# RELAY.net
KiCad netlist of a schematic drawn in Altium Designer
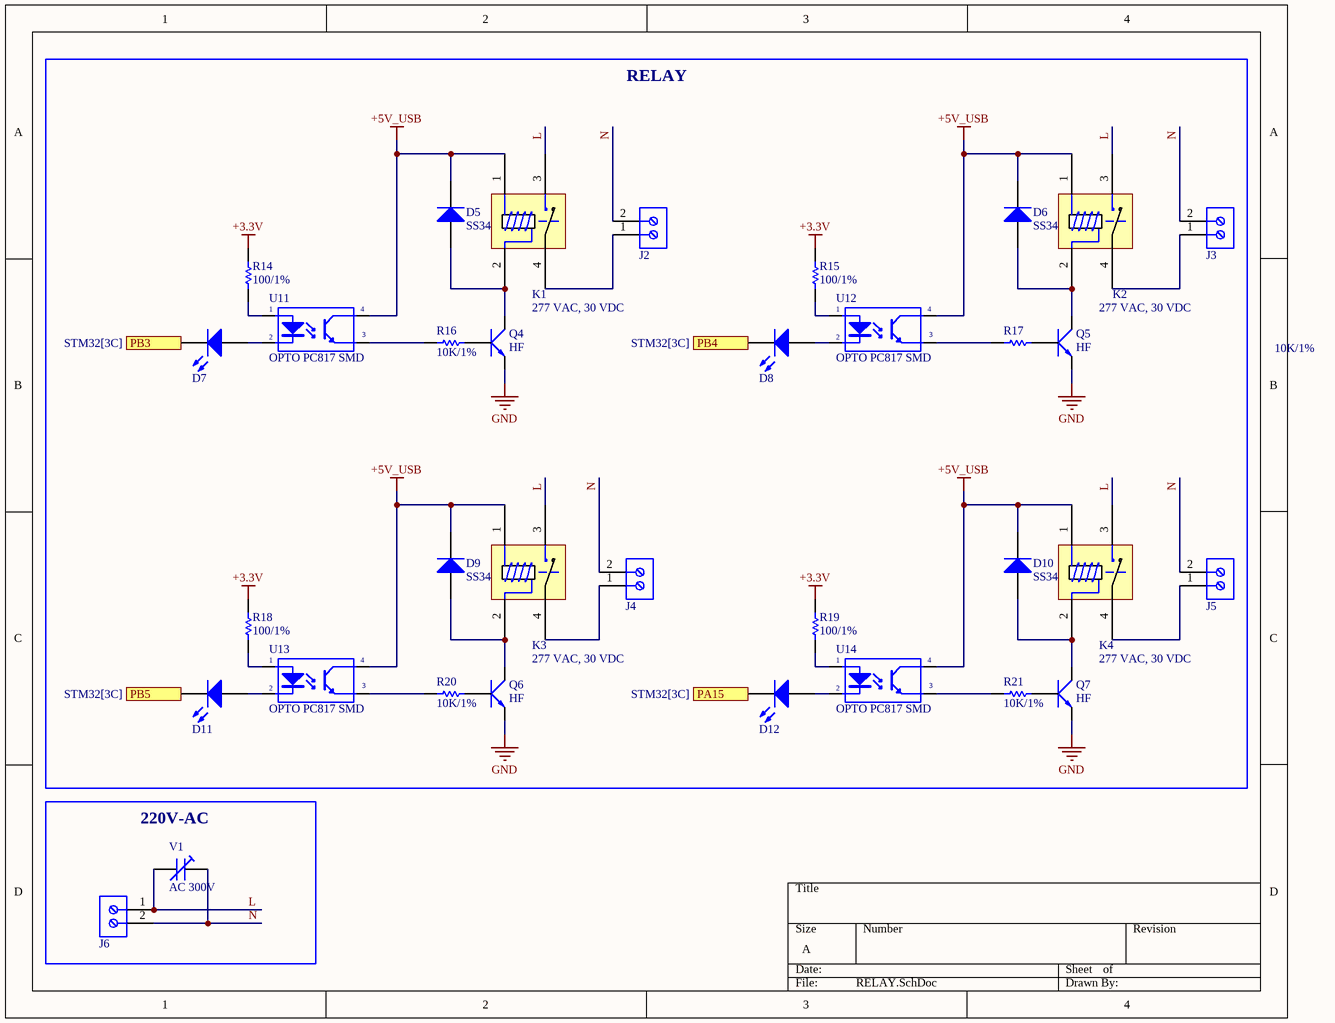
[diagram p0: RELAY.SchDoc]

(export (version "E")
  (design (tool "Eeschema 10.0.6"))
  (components
    (comp (ref "D5")
      (value "SS34")
      (footprint "DIODE SMA")
      (description "Dán")
      (libsource (lib "Altium_Lib_by_KhueNguyenCreator") (part "Diode SS34 ( 1N5822 )"))
    )
    (comp (ref "D6")
      (value "SS34")
      (footprint "DIODE SMA")
      (description "Dán")
      (libsource (lib "Altium_Lib_by_KhueNguyenCreator") (part "Diode SS34 ( 1N5822 )"))
    )
    (comp (ref "D7")
      (value "LED SMD")
      (footprint "LED_0805_Blue")
      (description "LED")
      (libsource (lib "PIF_Library") (part "LED SMD"))
    )
    (comp (ref "D8")
      (value "LED SMD")
      (footprint "LED_0805_Blue")
      (description "LED")
      (libsource (lib "PIF_Library") (part "LED SMD"))
    )
    (comp (ref "D9")
      (value "SS34")
      (footprint "DIODE SMA")
      (description "Dán")
      (libsource (lib "Altium_Lib_by_KhueNguyenCreator") (part "Diode SS34 ( 1N5822 )"))
    )
    (comp (ref "D10")
      (value "SS34")
      (footprint "DIODE SMA")
      (description "Dán")
      (libsource (lib "Altium_Lib_by_KhueNguyenCreator") (part "Diode SS34 ( 1N5822 )"))
    )
    (comp (ref "D11")
      (value "LED SMD")
      (footprint "LED_0805_Blue")
      (description "LED")
      (libsource (lib "PIF_Library") (part "LED SMD"))
    )
    (comp (ref "D12")
      (value "LED SMD")
      (footprint "LED_0805_Blue")
      (description "LED")
      (libsource (lib "PIF_Library") (part "LED SMD"))
    )
    (comp (ref "J2")
      (value "10A, 300V")
      (footprint "691214110002")
      (description "WR-TBL Series 2141 Horizontal Entry Modular, THT, pitch 3.5mm, 2p")
      (fields
        (field (name "MANUFACTURER PART NUMBER") "691214110002")
        (field (name "MANUFACTURER") "Wurth Elektronik")
      )
      (libsource (lib "Altium_Terminal_Block") (part "691214110002"))
    )
    (comp (ref "J3")
      (value "10A, 300V")
      (footprint "691214110002")
      (description "WR-TBL Series 2141 Horizontal Entry Modular, THT, pitch 3.5mm, 2p")
      (fields
        (field (name "MANUFACTURER PART NUMBER") "691214110002")
        (field (name "MANUFACTURER") "Wurth Elektronik")
      )
      (libsource (lib "Altium_Terminal_Block") (part "691214110002"))
    )
    (comp (ref "J4")
      (value "10A, 300V")
      (footprint "691214110002")
      (description "WR-TBL Series 2141 Horizontal Entry Modular, THT, pitch 3.5mm, 2p")
      (fields
        (field (name "MANUFACTURER PART NUMBER") "691214110002")
        (field (name "MANUFACTURER") "Wurth Elektronik")
      )
      (libsource (lib "Altium_Terminal_Block") (part "691214110002"))
    )
    (comp (ref "J5")
      (value "10A, 300V")
      (footprint "691214110002")
      (description "WR-TBL Series 2141 Horizontal Entry Modular, THT, pitch 3.5mm, 2p")
      (fields
        (field (name "MANUFACTURER PART NUMBER") "691214110002")
        (field (name "MANUFACTURER") "Wurth Elektronik")
      )
      (libsource (lib "Altium_Terminal_Block") (part "691214110002"))
    )
    (comp (ref "J6")
      (value "10A, 300V")
      (footprint "691214110002")
      (description "WR-TBL Series 2141 Horizontal Entry Modular, THT, pitch 3.5mm, 2p")
      (fields
        (field (name "MANUFACTURER PART NUMBER") "691214110002")
        (field (name "MANUFACTURER") "Wurth Elektronik")
      )
      (libsource (lib "Altium_Terminal_Block") (part "691214110002"))
    )
    (comp (ref "K1")
      (value "277 VAC, 30 VDC")
      (footprint "HF46F")
      (description "Coil Voltage: 12 VDC; Contact Current Rating: 7A; Switching Voltage Max: 277 VAC, 30 VDC")
      (libsource (lib "Altium_Relay") (part "HF46F-G 12-HS1"))
    )
    (comp (ref "K2")
      (value "277 VAC, 30 VDC")
      (footprint "HF46F")
      (description "Coil Voltage: 12 VDC; Contact Current Rating: 7A; Switching Voltage Max: 277 VAC, 30 VDC")
      (libsource (lib "Altium_Relay") (part "HF46F-G 12-HS1"))
    )
    (comp (ref "K3")
      (value "277 VAC, 30 VDC")
      (footprint "HF46F")
      (description "Coil Voltage: 12 VDC; Contact Current Rating: 7A; Switching Voltage Max: 277 VAC, 30 VDC")
      (libsource (lib "Altium_Relay") (part "HF46F-G 12-HS1"))
    )
    (comp (ref "K4")
      (value "277 VAC, 30 VDC")
      (footprint "HF46F")
      (description "Coil Voltage: 12 VDC; Contact Current Rating: 7A; Switching Voltage Max: 277 VAC, 30 VDC")
      (libsource (lib "Altium_Relay") (part "HF46F-G 12-HS1"))
    )
    (comp (ref "Q4")
      (value "HF")
      (footprint "SOT-23")
      (description "SOT-23")
      (libsource (lib "Altium_Lib_by_KhueNguyenCreator") (part "Trans C1815 HF SMD"))
    )
    (comp (ref "Q5")
      (value "HF")
      (footprint "SOT-23")
      (description "SOT-23")
      (libsource (lib "Altium_Lib_by_KhueNguyenCreator") (part "Trans C1815 HF SMD"))
    )
    (comp (ref "Q6")
      (value "HF")
      (footprint "SOT-23")
      (description "SOT-23")
      (libsource (lib "Altium_Lib_by_KhueNguyenCreator") (part "Trans C1815 HF SMD"))
    )
    (comp (ref "Q7")
      (value "HF")
      (footprint "SOT-23")
      (description "SOT-23")
      (libsource (lib "Altium_Lib_by_KhueNguyenCreator") (part "Trans C1815 HF SMD"))
    )
    (comp (ref "R14")
      (value "100/1%")
      (footprint "RES-SM-0805")
      (description "Resistor")
      (fields (field (name "Comment") "RESISTOR SMD"))
      (libsource (lib "PIF_Library") (part "RESISTOR SMD"))
    )
    (comp (ref "R15")
      (value "100/1%")
      (footprint "RES-SM-0805")
      (description "Resistor")
      (fields (field (name "Comment") "RESISTOR SMD"))
      (libsource (lib "PIF_Library") (part "RESISTOR SMD"))
    )
    (comp (ref "R16")
      (value "10K/1%")
      (footprint "RES-SM-0805")
      (description "Resistor")
      (fields (field (name "Comment") "RESISTOR SMD"))
      (libsource (lib "PIF_Library") (part "RESISTOR SMD"))
    )
    (comp (ref "R17")
      (value "10K/1%")
      (footprint "RES-SM-0805")
      (description "Resistor")
      (fields (field (name "Comment") "RESISTOR SMD"))
      (libsource (lib "PIF_Library") (part "RESISTOR SMD"))
    )
    (comp (ref "R18")
      (value "100/1%")
      (footprint "RES-SM-0805")
      (description "Resistor")
      (fields (field (name "Comment") "RESISTOR SMD"))
      (libsource (lib "PIF_Library") (part "RESISTOR SMD"))
    )
    (comp (ref "R19")
      (value "100/1%")
      (footprint "RES-SM-0805")
      (description "Resistor")
      (fields (field (name "Comment") "RESISTOR SMD"))
      (libsource (lib "PIF_Library") (part "RESISTOR SMD"))
    )
    (comp (ref "R20")
      (value "10K/1%")
      (footprint "RES-SM-0805")
      (description "Resistor")
      (fields (field (name "Comment") "RESISTOR SMD"))
      (libsource (lib "PIF_Library") (part "RESISTOR SMD"))
    )
    (comp (ref "R21")
      (value "10K/1%")
      (footprint "RES-SM-0805")
      (description "Resistor")
      (fields (field (name "Comment") "RESISTOR SMD"))
      (libsource (lib "PIF_Library") (part "RESISTOR SMD"))
    )
    (comp (ref "U11")
      (value "OPTO PC817 SMD")
      (footprint "SOP4")
      (description "Single Opto")
      (libsource (lib "Altium_Lib_by_KhueNguyenCreator") (part "OPTO PC817 SMD"))
    )
    (comp (ref "U12")
      (value "OPTO PC817 SMD")
      (footprint "SOP4")
      (description "Single Opto")
      (libsource (lib "Altium_Lib_by_KhueNguyenCreator") (part "OPTO PC817 SMD"))
    )
    (comp (ref "U13")
      (value "OPTO PC817 SMD")
      (footprint "SOP4")
      (description "Single Opto")
      (libsource (lib "Altium_Lib_by_KhueNguyenCreator") (part "OPTO PC817 SMD"))
    )
    (comp (ref "U14")
      (value "OPTO PC817 SMD")
      (footprint "SOP4")
      (description "Single Opto")
      (libsource (lib "Altium_Lib_by_KhueNguyenCreator") (part "OPTO PC817 SMD"))
    )
    (comp (ref "V1")
      (value "AC 300V")
      (footprint "Varistor")
      (description "Varistors 7D471K AC 300V")
      (fields (field (name "TOLERANCE") "+/- 10%") (field (name "VOLTAGE") "300V"))
      (libsource (lib "Altium_Varistors") (part "05000730110"))
    )
  )
  (nets
    (net (code "1") (name "+3.3V") (class "Default")
      (node (ref "R14") (pin "2") (pinfunction "2_2") (pintype "passive"))
      (node (ref "R15") (pin "2") (pinfunction "2_2") (pintype "passive"))
      (node (ref "R18") (pin "2") (pinfunction "2_2") (pintype "passive"))
      (node (ref "R19") (pin "2") (pinfunction "2_2") (pintype "passive"))
    )
    (net (code "2") (name "+5V_USB") (class "Default")
      (node (ref "D10") (pin "2") (pinfunction "K_2") (pintype "passive"))
      (node (ref "D5") (pin "2") (pinfunction "K_2") (pintype "passive"))
      (node (ref "D6") (pin "2") (pinfunction "K_2") (pintype "passive"))
      (node (ref "D9") (pin "2") (pinfunction "K_2") (pintype "passive"))
      (node (ref "K1") (pin "1") (pinfunction "Coil_1") (pintype "passive"))
      (node (ref "K2") (pin "1") (pinfunction "Coil_1") (pintype "passive"))
      (node (ref "K3") (pin "1") (pinfunction "Coil_1") (pintype "passive"))
      (node (ref "K4") (pin "1") (pinfunction "Coil_1") (pintype "passive"))
      (node (ref "U11") (pin "4") (pinfunction "C_4") (pintype "passive"))
      (node (ref "U12") (pin "4") (pinfunction "C_4") (pintype "passive"))
      (node (ref "U13") (pin "4") (pinfunction "C_4") (pintype "passive"))
      (node (ref "U14") (pin "4") (pinfunction "C_4") (pintype "passive"))
    )
    (net (code "4") (name "/L") (class "Default")
      (node (ref "J6") (pin "1") (pinfunction "1_1") (pintype "passive"))
      (node (ref "K1") (pin "3") (pinfunction "NO_3") (pintype "passive"))
      (node (ref "K2") (pin "3") (pinfunction "NO_3") (pintype "passive"))
      (node (ref "K3") (pin "3") (pinfunction "NO_3") (pintype "passive"))
      (node (ref "K4") (pin "3") (pinfunction "NO_3") (pintype "passive"))
      (node (ref "V1") (pin "1") (pinfunction "1_1") (pintype "passive"))
    )
    (net (code "5") (name "/N") (class "Default")
      (node (ref "J2") (pin "2") (pinfunction "2_2") (pintype "passive"))
      (node (ref "J3") (pin "2") (pinfunction "2_2") (pintype "passive"))
      (node (ref "J4") (pin "2") (pinfunction "2_2") (pintype "passive"))
      (node (ref "J5") (pin "2") (pinfunction "2_2") (pintype "passive"))
      (node (ref "J6") (pin "2") (pinfunction "2_2") (pintype "passive"))
      (node (ref "V1") (pin "2") (pinfunction "2_2") (pintype "passive"))
    )
    (net (code "6") (name "/PA15") (class "Default")
      (node (ref "D12") (pin "2") (pinfunction "K_2") (pintype "passive"))
    )
    (net (code "7") (name "/PB3") (class "Default")
      (node (ref "D7") (pin "2") (pinfunction "K_2") (pintype "passive"))
    )
    (net (code "8") (name "/PB4") (class "Default")
      (node (ref "D8") (pin "2") (pinfunction "K_2") (pintype "passive"))
    )
    (net (code "9") (name "/PB5") (class "Default")
      (node (ref "D11") (pin "2") (pinfunction "K_2") (pintype "passive"))
    )
    (net (code "10") (name "GND") (class "Default")
      (node (ref "Q4") (pin "2") (pinfunction "E_2") (pintype "passive"))
      (node (ref "Q5") (pin "2") (pinfunction "E_2") (pintype "passive"))
      (node (ref "Q6") (pin "2") (pinfunction "E_2") (pintype "passive"))
      (node (ref "Q7") (pin "2") (pinfunction "E_2") (pintype "passive"))
    )
    (net (code "11") (name "Net-(D5-A)") (class "Default")
      (node (ref "D5") (pin "1") (pinfunction "A_1") (pintype "passive"))
      (node (ref "K1") (pin "2") (pinfunction "Coil_2") (pintype "passive"))
      (node (ref "Q4") (pin "3") (pinfunction "C_3") (pintype "passive"))
    )
    (net (code "12") (name "Net-(D6-A)") (class "Default")
      (node (ref "D6") (pin "1") (pinfunction "A_1") (pintype "passive"))
      (node (ref "K2") (pin "2") (pinfunction "Coil_2") (pintype "passive"))
      (node (ref "Q5") (pin "3") (pinfunction "C_3") (pintype "passive"))
    )
    (net (code "13") (name "Net-(D7-A)") (class "Default")
      (node (ref "D7") (pin "1") (pinfunction "A_1") (pintype "passive"))
      (node (ref "U11") (pin "2") (pinfunction "K_2") (pintype "passive"))
    )
    (net (code "14") (name "Net-(D8-A)") (class "Default")
      (node (ref "D8") (pin "1") (pinfunction "A_1") (pintype "passive"))
      (node (ref "U12") (pin "2") (pinfunction "K_2") (pintype "passive"))
    )
    (net (code "15") (name "Net-(D9-A)") (class "Default")
      (node (ref "D9") (pin "1") (pinfunction "A_1") (pintype "passive"))
      (node (ref "K3") (pin "2") (pinfunction "Coil_2") (pintype "passive"))
      (node (ref "Q6") (pin "3") (pinfunction "C_3") (pintype "passive"))
    )
    (net (code "16") (name "Net-(D10-A)") (class "Default")
      (node (ref "D10") (pin "1") (pinfunction "A_1") (pintype "passive"))
      (node (ref "K4") (pin "2") (pinfunction "Coil_2") (pintype "passive"))
      (node (ref "Q7") (pin "3") (pinfunction "C_3") (pintype "passive"))
    )
    (net (code "17") (name "Net-(D11-A)") (class "Default")
      (node (ref "D11") (pin "1") (pinfunction "A_1") (pintype "passive"))
      (node (ref "U13") (pin "2") (pinfunction "K_2") (pintype "passive"))
    )
    (net (code "18") (name "Net-(D12-A)") (class "Default")
      (node (ref "D12") (pin "1") (pinfunction "A_1") (pintype "passive"))
      (node (ref "U14") (pin "2") (pinfunction "K_2") (pintype "passive"))
    )
    (net (code "19") (name "Net-(J2-Pad1)") (class "Default")
      (node (ref "J2") (pin "1") (pinfunction "1_1") (pintype "passive"))
      (node (ref "K1") (pin "4") (pintype "passive"))
    )
    (net (code "20") (name "Net-(J3-Pad1)") (class "Default")
      (node (ref "J3") (pin "1") (pinfunction "1_1") (pintype "passive"))
      (node (ref "K2") (pin "4") (pintype "passive"))
    )
    (net (code "21") (name "Net-(J4-Pad1)") (class "Default")
      (node (ref "J4") (pin "1") (pinfunction "1_1") (pintype "passive"))
      (node (ref "K3") (pin "4") (pintype "passive"))
    )
    (net (code "22") (name "Net-(J5-Pad1)") (class "Default")
      (node (ref "J5") (pin "1") (pinfunction "1_1") (pintype "passive"))
      (node (ref "K4") (pin "4") (pintype "passive"))
    )
    (net (code "23") (name "Net-(Q4-B)") (class "Default")
      (node (ref "Q4") (pin "1") (pinfunction "B_1") (pintype "passive"))
      (node (ref "R16") (pin "1") (pinfunction "1_1") (pintype "passive"))
    )
    (net (code "24") (name "Net-(Q5-B)") (class "Default")
      (node (ref "Q5") (pin "1") (pinfunction "B_1") (pintype "passive"))
      (node (ref "R17") (pin "1") (pinfunction "1_1") (pintype "passive"))
    )
    (net (code "25") (name "Net-(Q6-B)") (class "Default")
      (node (ref "Q6") (pin "1") (pinfunction "B_1") (pintype "passive"))
      (node (ref "R20") (pin "1") (pinfunction "1_1") (pintype "passive"))
    )
    (net (code "26") (name "Net-(Q7-B)") (class "Default")
      (node (ref "Q7") (pin "1") (pinfunction "B_1") (pintype "passive"))
      (node (ref "R21") (pin "1") (pinfunction "1_1") (pintype "passive"))
    )
    (net (code "27") (name "Net-(U11-A)") (class "Default")
      (node (ref "R14") (pin "1") (pinfunction "1_1") (pintype "passive"))
      (node (ref "U11") (pin "1") (pinfunction "A_1") (pintype "passive"))
    )
    (net (code "28") (name "Net-(U11-E)") (class "Default")
      (node (ref "R16") (pin "2") (pinfunction "2_2") (pintype "passive"))
      (node (ref "U11") (pin "3") (pinfunction "E_3") (pintype "passive"))
    )
    (net (code "29") (name "Net-(U12-A)") (class "Default")
      (node (ref "R15") (pin "1") (pinfunction "1_1") (pintype "passive"))
      (node (ref "U12") (pin "1") (pinfunction "A_1") (pintype "passive"))
    )
    (net (code "30") (name "Net-(U12-E)") (class "Default")
      (node (ref "R17") (pin "2") (pinfunction "2_2") (pintype "passive"))
      (node (ref "U12") (pin "3") (pinfunction "E_3") (pintype "passive"))
    )
    (net (code "31") (name "Net-(U13-A)") (class "Default")
      (node (ref "R18") (pin "1") (pinfunction "1_1") (pintype "passive"))
      (node (ref "U13") (pin "1") (pinfunction "A_1") (pintype "passive"))
    )
    (net (code "32") (name "Net-(U13-E)") (class "Default")
      (node (ref "R20") (pin "2") (pinfunction "2_2") (pintype "passive"))
      (node (ref "U13") (pin "3") (pinfunction "E_3") (pintype "passive"))
    )
    (net (code "33") (name "Net-(U14-A)") (class "Default")
      (node (ref "R19") (pin "1") (pinfunction "1_1") (pintype "passive"))
      (node (ref "U14") (pin "1") (pinfunction "A_1") (pintype "passive"))
    )
    (net (code "34") (name "Net-(U14-E)") (class "Default")
      (node (ref "R21") (pin "2") (pinfunction "2_2") (pintype "passive"))
      (node (ref "U14") (pin "3") (pinfunction "E_3") (pintype "passive"))
    )
  )
)
